# RF_A.net
KiCad netlist of a schematic drawn in Altium Designer
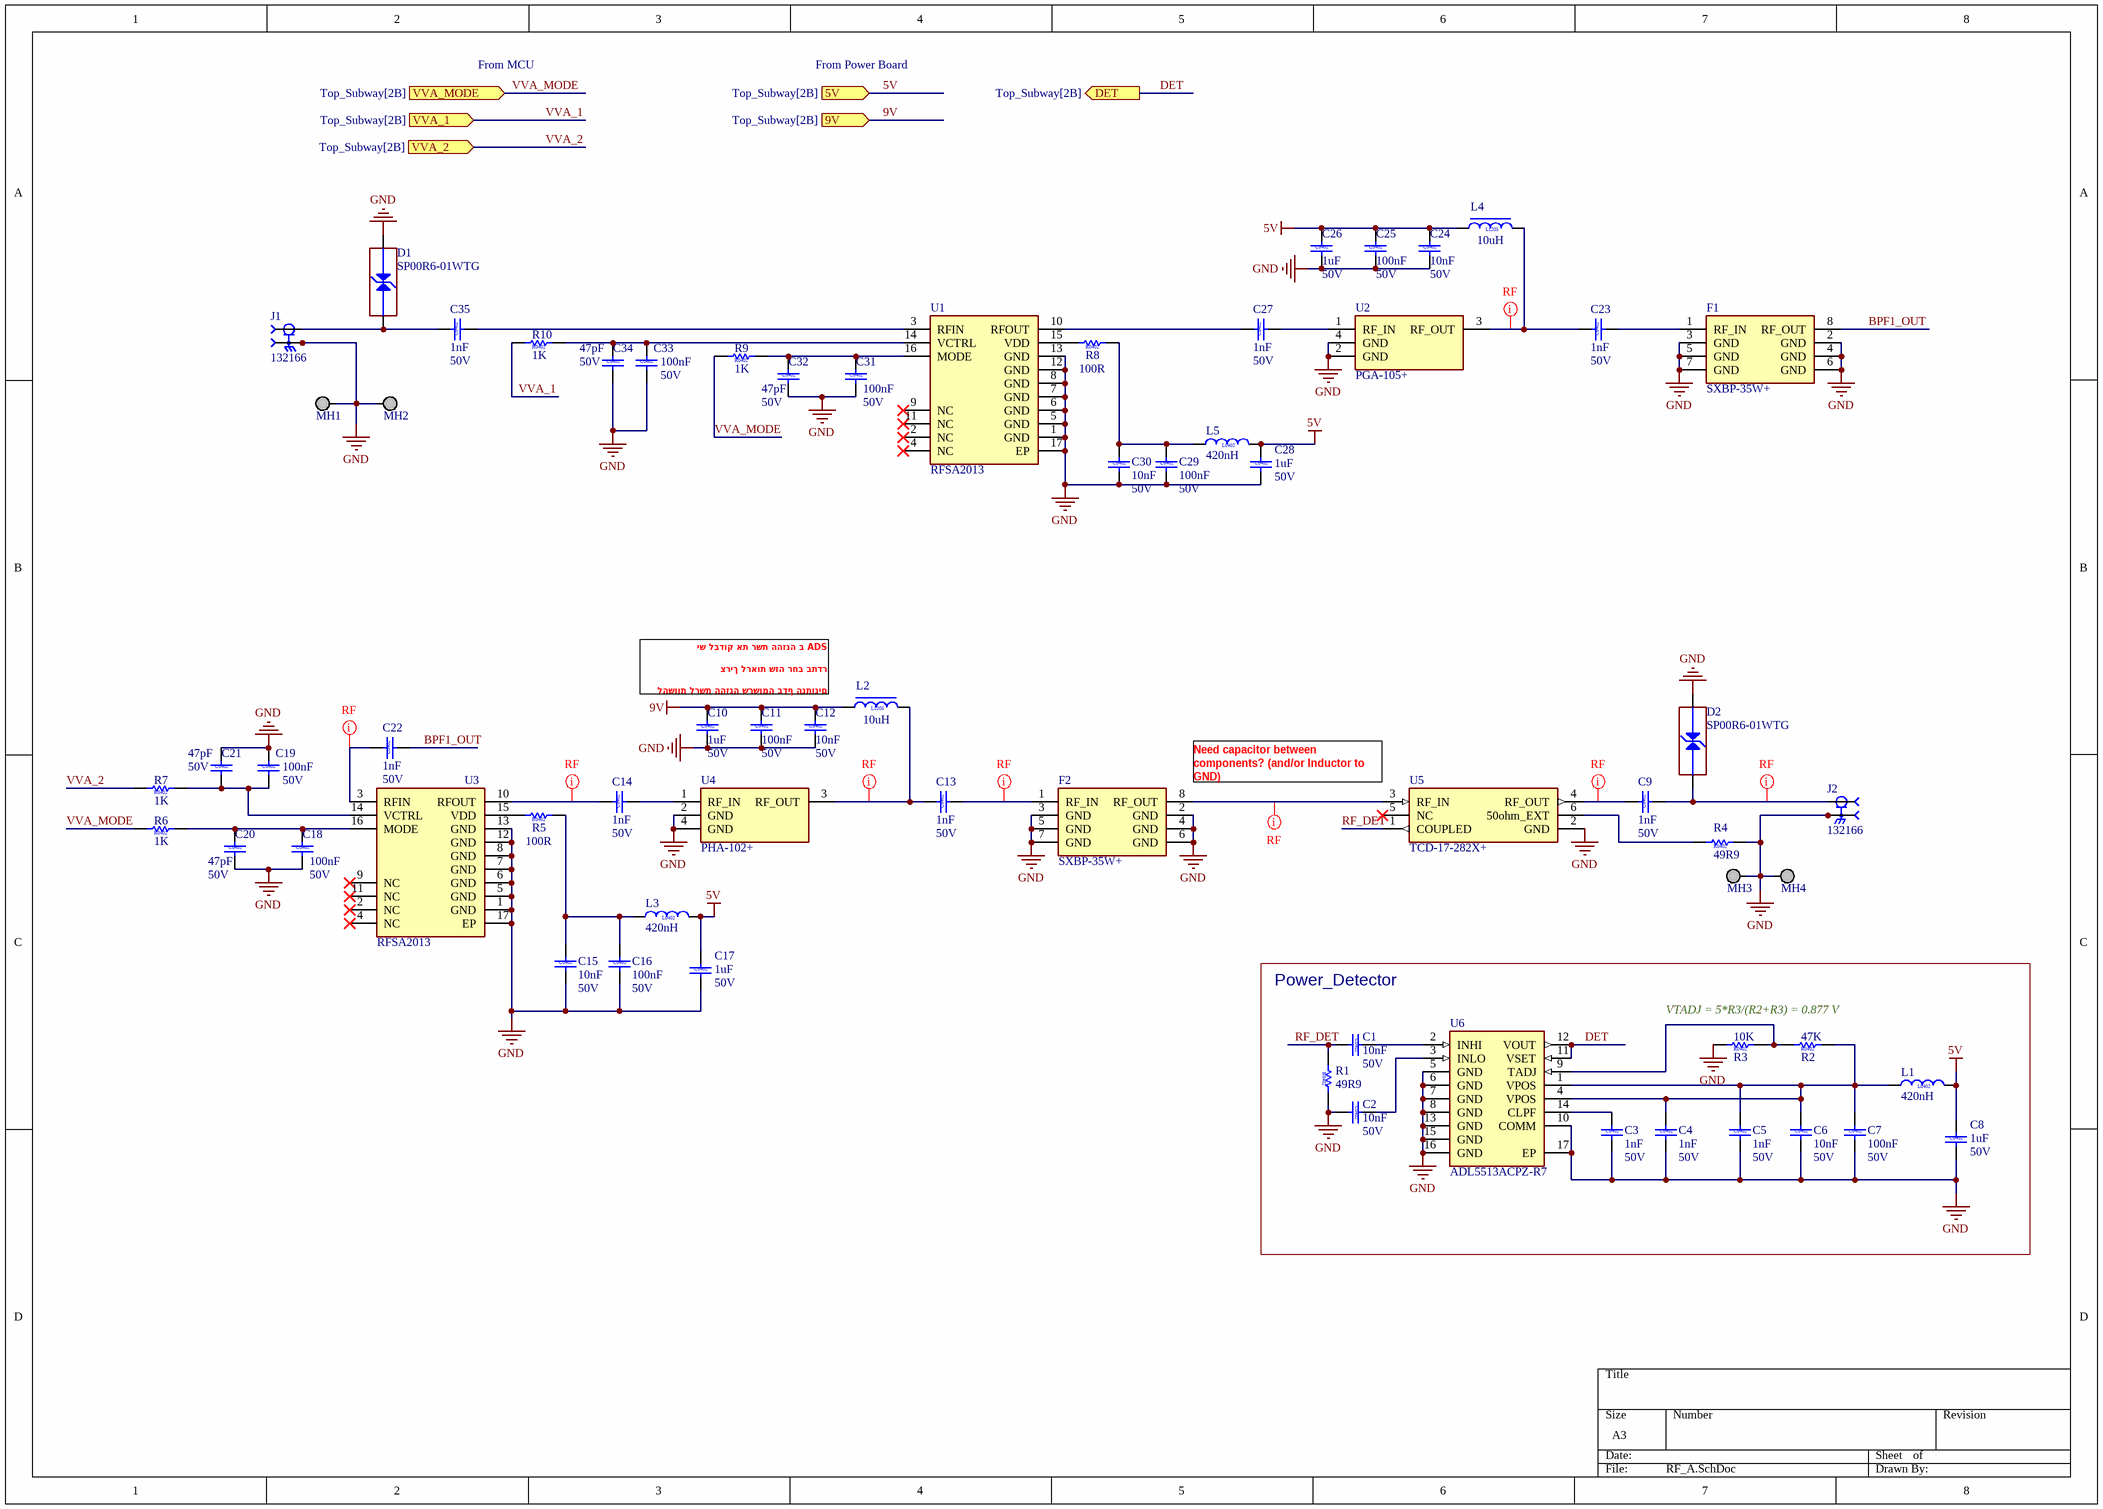
[diagram p0: RF_A.SchDoc]

(export (version "E")
  (design (tool "Eeschema 10.0.6"))
  (components
    (comp (ref "C1")
      (value "10nF")
      (footprint "C0402")
      (description "Capacitor, MLCC, 10nF, 50V, X7R, 10%, 0402, T=0.5mm")
      (fields
        (field (name "MANUFACTURER_PART_NUMBER") "GRM155R71H103KA88D")
        (field (name "MANUFACTURER") "MURATA")
        (field (name "VOLTAGE_RATING") "50V")
      )
      (libsource (lib "CAP_Lib") (part "CAP-103"))
    )
    (comp (ref "C2")
      (value "10nF")
      (footprint "C0402")
      (description "Capacitor, MLCC, 10nF, 50V, X7R, 10%, 0402, T=0.5mm")
      (fields
        (field (name "MANUFACTURER_PART_NUMBER") "GRM155R71H103KA88D")
        (field (name "MANUFACTURER") "MURATA")
        (field (name "VOLTAGE_RATING") "50V")
      )
      (libsource (lib "CAP_Lib") (part "CAP-103"))
    )
    (comp (ref "C3")
      (value "1nF")
      (footprint "C0402")
      (description "Capacitor, MLCC, 1nF, 50V, X7R, 10%, 0402, T=0.5mm")
      (fields
        (field (name "MANUFACTURER_PART_NUMBER") "GRM155R71H102KA01D")
        (field (name "MANUFACTURER") "MURATA")
        (field (name "VOLTAGE_RATING") "50V")
      )
      (libsource (lib "CAP_Lib") (part "CAP-102"))
    )
    (comp (ref "C4")
      (value "1nF")
      (footprint "C0402")
      (description "Capacitor, MLCC, 1nF, 50V, X7R, 10%, 0402, T=0.5mm")
      (fields
        (field (name "MANUFACTURER_PART_NUMBER") "GRM155R71H102KA01D")
        (field (name "MANUFACTURER") "MURATA")
        (field (name "VOLTAGE_RATING") "50V")
      )
      (libsource (lib "CAP_Lib") (part "CAP-102"))
    )
    (comp (ref "C5")
      (value "1nF")
      (footprint "C0402")
      (description "Capacitor, MLCC, 1nF, 50V, X7R, 10%, 0402, T=0.5mm")
      (fields
        (field (name "MANUFACTURER_PART_NUMBER") "GRM155R71H102KA01D")
        (field (name "MANUFACTURER") "MURATA")
        (field (name "VOLTAGE_RATING") "50V")
      )
      (libsource (lib "CAP_Lib") (part "CAP-102"))
    )
    (comp (ref "C6")
      (value "10nF")
      (footprint "C0402")
      (description "Capacitor, MLCC, 10nF, 50V, X7R, 10%, 0402, T=0.5mm")
      (fields
        (field (name "MANUFACTURER_PART_NUMBER") "GRM155R71H103KA88D")
        (field (name "MANUFACTURER") "MURATA")
        (field (name "VOLTAGE_RATING") "50V")
      )
      (libsource (lib "CAP_Lib") (part "CAP-103"))
    )
    (comp (ref "C7")
      (value "100nF")
      (footprint "C0402")
      (description "Capacitor, MLCC, 100nF, 50V, X7R, 10%, 0402, T=0.5mm")
      (fields
        (field (name "MANUFACTURER_PART_NUMBER") "GRM155R71H104KE14D")
        (field (name "MANUFACTURER") "MURATA")
        (field (name "VOLTAGE_RATING") "50V")
      )
      (libsource (lib "CAP_Lib") (part "CAP-104"))
    )
    (comp (ref "C8")
      (value "1uF")
      (footprint "C0402")
      (description "Capacitor, MLCC, 1uF, 50V, X5R, 10%, 0402, T=0.5mm")
      (fields
        (field (name "MANUFACTURER_PART_NUMBER") "GRM155R61H105KE05D")
        (field (name "MANUFACTURER") "MURATA")
        (field (name "VOLTAGE_RATING") "50V")
      )
      (libsource (lib "CAP_Lib") (part "CAP-001"))
    )
    (comp (ref "C9")
      (value "1nF")
      (footprint "C0402")
      (description "Capacitor, MLCC, 1nF, 50V, X7R, 10%, 0402, T=0.5mm")
      (fields
        (field (name "MANUFACTURER_PART_NUMBER") "GRM155R71H102KA01D")
        (field (name "MANUFACTURER") "MURATA")
        (field (name "VOLTAGE_RATING") "50V")
      )
      (libsource (lib "CAP_Lib") (part "CAP-102"))
    )
    (comp (ref "C10")
      (value "1uF")
      (footprint "C0402")
      (description "Capacitor, MLCC, 1uF, 50V, X5R, 10%, 0402, T=0.5mm")
      (fields
        (field (name "MANUFACTURER_PART_NUMBER") "GRM155R61H105KE05D")
        (field (name "MANUFACTURER") "MURATA")
        (field (name "VOLTAGE_RATING") "50V")
      )
      (libsource (lib "CAP_Lib") (part "CAP-001"))
    )
    (comp (ref "C11")
      (value "100nF")
      (footprint "C0402")
      (description "Capacitor, MLCC, 100nF, 50V, X7R, 10%, 0402, T=0.5mm")
      (fields
        (field (name "MANUFACTURER_PART_NUMBER") "GRM155R71H104KE14D")
        (field (name "MANUFACTURER") "MURATA")
        (field (name "VOLTAGE_RATING") "50V")
      )
      (libsource (lib "CAP_Lib") (part "CAP-104"))
    )
    (comp (ref "C12")
      (value "10nF")
      (footprint "C0402")
      (description "Capacitor, MLCC, 10nF, 50V, X7R, 10%, 0402, T=0.5mm")
      (fields
        (field (name "MANUFACTURER_PART_NUMBER") "GRM155R71H103KA88D")
        (field (name "MANUFACTURER") "MURATA")
        (field (name "VOLTAGE_RATING") "50V")
      )
      (libsource (lib "CAP_Lib") (part "CAP-103"))
    )
    (comp (ref "C13")
      (value "1nF")
      (footprint "C0402")
      (description "Capacitor, MLCC, 1nF, 50V, X7R, 10%, 0402, T=0.5mm")
      (fields
        (field (name "MANUFACTURER_PART_NUMBER") "GRM155R71H102KA01D")
        (field (name "MANUFACTURER") "MURATA")
        (field (name "VOLTAGE_RATING") "50V")
      )
      (libsource (lib "CAP_Lib") (part "CAP-102"))
    )
    (comp (ref "C14")
      (value "1nF")
      (footprint "C0402")
      (description "Capacitor, MLCC, 1nF, 50V, X7R, 10%, 0402, T=0.5mm")
      (fields
        (field (name "MANUFACTURER_PART_NUMBER") "GRM155R71H102KA01D")
        (field (name "MANUFACTURER") "MURATA")
        (field (name "VOLTAGE_RATING") "50V")
      )
      (libsource (lib "CAP_Lib") (part "CAP-102"))
    )
    (comp (ref "C15")
      (value "10nF")
      (footprint "C0402")
      (description "Capacitor, MLCC, 10nF, 50V, X7R, 10%, 0402, T=0.5mm")
      (fields
        (field (name "MANUFACTURER_PART_NUMBER") "GRM155R71H103KA88D")
        (field (name "MANUFACTURER") "MURATA")
        (field (name "VOLTAGE_RATING") "50V")
      )
      (libsource (lib "CAP_Lib") (part "CAP-103"))
    )
    (comp (ref "C16")
      (value "100nF")
      (footprint "C0402")
      (description "Capacitor, MLCC, 100nF, 50V, X7R, 10%, 0402, T=0.5mm")
      (fields
        (field (name "MANUFACTURER_PART_NUMBER") "GRM155R71H104KE14D")
        (field (name "MANUFACTURER") "MURATA")
        (field (name "VOLTAGE_RATING") "50V")
      )
      (libsource (lib "CAP_Lib") (part "CAP-104"))
    )
    (comp (ref "C17")
      (value "1uF")
      (footprint "C0402")
      (description "Capacitor, MLCC, 1uF, 50V, X5R, 10%, 0402, T=0.5mm")
      (fields
        (field (name "MANUFACTURER_PART_NUMBER") "GRM155R61H105KE05D")
        (field (name "MANUFACTURER") "MURATA")
        (field (name "VOLTAGE_RATING") "50V")
      )
      (libsource (lib "CAP_Lib") (part "CAP-001"))
    )
    (comp (ref "C18")
      (value "100nF")
      (footprint "C0402")
      (description "Capacitor, MLCC, 100nF, 50V, X7R, 10%, 0402, T=0.5mm")
      (fields
        (field (name "MANUFACTURER_PART_NUMBER") "GRM155R71H104KE14D")
        (field (name "MANUFACTURER") "MURATA")
        (field (name "VOLTAGE_RATING") "50V")
      )
      (libsource (lib "CAP_Lib") (part "CAP-104"))
    )
    (comp (ref "C19")
      (value "100nF")
      (footprint "C0402")
      (description "Capacitor, MLCC, 100nF, 50V, X7R, 10%, 0402, T=0.5mm")
      (fields
        (field (name "MANUFACTURER_PART_NUMBER") "GRM155R71H104KE14D")
        (field (name "MANUFACTURER") "MURATA")
        (field (name "VOLTAGE_RATING") "50V")
      )
      (libsource (lib "CAP_Lib") (part "CAP-104"))
    )
    (comp (ref "C20")
      (value "47pF")
      (footprint "C0402")
      (description "Capacitor, MLCC, 47pF, 50V, C0G 2%, 0402, T=0.5mm")
      (fields
        (field (name "MANUFACTURER_PART_NUMBER") "GRM1555C1H470FA01D")
        (field (name "MANUFACTURER") "MURATA")
        (field (name "VOLTAGE_RATING") "50V")
      )
      (libsource (lib "CAP_Lib") (part "CAP-207"))
    )
    (comp (ref "C21")
      (value "47pF")
      (footprint "C0402")
      (description "Capacitor, MLCC, 47pF, 50V, C0G 2%, 0402, T=0.5mm")
      (fields
        (field (name "MANUFACTURER_PART_NUMBER") "GRM1555C1H470FA01D")
        (field (name "MANUFACTURER") "MURATA")
        (field (name "VOLTAGE_RATING") "50V")
      )
      (libsource (lib "CAP_Lib") (part "CAP-207"))
    )
    (comp (ref "C22")
      (value "1nF")
      (footprint "C0402")
      (description "Capacitor, MLCC, 1nF, 50V, X7R, 10%, 0402, T=0.5mm")
      (fields
        (field (name "MANUFACTURER_PART_NUMBER") "GRM155R71H102KA01D")
        (field (name "MANUFACTURER") "MURATA")
        (field (name "VOLTAGE_RATING") "50V")
      )
      (libsource (lib "CAP_Lib") (part "CAP-102"))
    )
    (comp (ref "C23")
      (value "1nF")
      (footprint "C0402")
      (description "Capacitor, MLCC, 1nF, 50V, X7R, 10%, 0402, T=0.5mm")
      (fields
        (field (name "MANUFACTURER_PART_NUMBER") "GRM155R71H102KA01D")
        (field (name "MANUFACTURER") "MURATA")
        (field (name "VOLTAGE_RATING") "50V")
      )
      (libsource (lib "CAP_Lib") (part "CAP-102"))
    )
    (comp (ref "C24")
      (value "10nF")
      (footprint "C0402")
      (description "Capacitor, MLCC, 10nF, 50V, X7R, 10%, 0402, T=0.5mm")
      (fields
        (field (name "MANUFACTURER_PART_NUMBER") "GRM155R71H103KA88D")
        (field (name "MANUFACTURER") "MURATA")
        (field (name "VOLTAGE_RATING") "50V")
      )
      (libsource (lib "CAP_Lib") (part "CAP-103"))
    )
    (comp (ref "C25")
      (value "100nF")
      (footprint "C0402")
      (description "Capacitor, MLCC, 100nF, 50V, X7R, 10%, 0402, T=0.5mm")
      (fields
        (field (name "MANUFACTURER_PART_NUMBER") "GRM155R71H104KE14D")
        (field (name "MANUFACTURER") "MURATA")
        (field (name "VOLTAGE_RATING") "50V")
      )
      (libsource (lib "CAP_Lib") (part "CAP-104"))
    )
    (comp (ref "C26")
      (value "1uF")
      (footprint "C0402")
      (description "Capacitor, MLCC, 1uF, 50V, X5R, 10%, 0402, T=0.5mm")
      (fields
        (field (name "MANUFACTURER_PART_NUMBER") "GRM155R61H105KE05D")
        (field (name "MANUFACTURER") "MURATA")
        (field (name "VOLTAGE_RATING") "50V")
      )
      (libsource (lib "CAP_Lib") (part "CAP-001"))
    )
    (comp (ref "C27")
      (value "1nF")
      (footprint "C0402")
      (description "Capacitor, MLCC, 1nF, 50V, X7R, 10%, 0402, T=0.5mm")
      (fields
        (field (name "MANUFACTURER_PART_NUMBER") "GRM155R71H102KA01D")
        (field (name "MANUFACTURER") "MURATA")
        (field (name "VOLTAGE_RATING") "50V")
      )
      (libsource (lib "CAP_Lib") (part "CAP-102"))
    )
    (comp (ref "C28")
      (value "1uF")
      (footprint "C0402")
      (description "Capacitor, MLCC, 1uF, 50V, X5R, 10%, 0402, T=0.5mm")
      (fields
        (field (name "MANUFACTURER_PART_NUMBER") "GRM155R61H105KE05D")
        (field (name "MANUFACTURER") "MURATA")
        (field (name "VOLTAGE_RATING") "50V")
      )
      (libsource (lib "CAP_Lib") (part "CAP-001"))
    )
    (comp (ref "C29")
      (value "100nF")
      (footprint "C0402")
      (description "Capacitor, MLCC, 100nF, 50V, X7R, 10%, 0402, T=0.5mm")
      (fields
        (field (name "MANUFACTURER_PART_NUMBER") "GRM155R71H104KE14D")
        (field (name "MANUFACTURER") "MURATA")
        (field (name "VOLTAGE_RATING") "50V")
      )
      (libsource (lib "CAP_Lib") (part "CAP-104"))
    )
    (comp (ref "C30")
      (value "10nF")
      (footprint "C0402")
      (description "Capacitor, MLCC, 10nF, 50V, X7R, 10%, 0402, T=0.5mm")
      (fields
        (field (name "MANUFACTURER_PART_NUMBER") "GRM155R71H103KA88D")
        (field (name "MANUFACTURER") "MURATA")
        (field (name "VOLTAGE_RATING") "50V")
      )
      (libsource (lib "CAP_Lib") (part "CAP-103"))
    )
    (comp (ref "C31")
      (value "100nF")
      (footprint "C0402")
      (description "Capacitor, MLCC, 100nF, 50V, X7R, 10%, 0402, T=0.5mm")
      (fields
        (field (name "MANUFACTURER_PART_NUMBER") "GRM155R71H104KE14D")
        (field (name "MANUFACTURER") "MURATA")
        (field (name "VOLTAGE_RATING") "50V")
      )
      (libsource (lib "CAP_Lib") (part "CAP-104"))
    )
    (comp (ref "C32")
      (value "47pF")
      (footprint "C0402")
      (description "Capacitor, MLCC, 47pF, 50V, C0G 2%, 0402, T=0.5mm")
      (fields
        (field (name "MANUFACTURER_PART_NUMBER") "GRM1555C1H470FA01D")
        (field (name "MANUFACTURER") "MURATA")
        (field (name "VOLTAGE_RATING") "50V")
      )
      (libsource (lib "CAP_Lib") (part "CAP-207"))
    )
    (comp (ref "C33")
      (value "100nF")
      (footprint "C0402")
      (description "Capacitor, MLCC, 100nF, 50V, X7R, 10%, 0402, T=0.5mm")
      (fields
        (field (name "MANUFACTURER_PART_NUMBER") "GRM155R71H104KE14D")
        (field (name "MANUFACTURER") "MURATA")
        (field (name "VOLTAGE_RATING") "50V")
      )
      (libsource (lib "CAP_Lib") (part "CAP-104"))
    )
    (comp (ref "C34")
      (value "47pF")
      (footprint "C0402")
      (description "Capacitor, MLCC, 47pF, 50V, C0G 2%, 0402, T=0.5mm")
      (fields
        (field (name "MANUFACTURER_PART_NUMBER") "GRM1555C1H470FA01D")
        (field (name "MANUFACTURER") "MURATA")
        (field (name "VOLTAGE_RATING") "50V")
      )
      (libsource (lib "CAP_Lib") (part "CAP-207"))
    )
    (comp (ref "C35")
      (value "1nF")
      (footprint "C0402")
      (description "Capacitor, MLCC, 1nF, 50V, X7R, 10%, 0402, T=0.5mm")
      (fields
        (field (name "MANUFACTURER_PART_NUMBER") "GRM155R71H102KA01D")
        (field (name "MANUFACTURER") "MURATA")
        (field (name "VOLTAGE_RATING") "50V")
      )
      (libsource (lib "CAP_Lib") (part "CAP-102"))
    )
    (comp (ref "D1")
      (value "SP00R6-01WTG")
      (footprint "DIO_TVS_FLIPCHIP2")
      (description "Diode, TVS, Bidirectional, 0.3V working, 0.7V breakdown, 2.5V clamping, 3A")
      (fields
        (field (name "MANUFACTURER") "Littelfuse")
        (field (name "MOUSER PART NUMBER") "576-SP00R6-01WTG")
      )
      (libsource (lib "DIO_Lib") (part "DIO-012"))
    )
    (comp (ref "D2")
      (value "SP00R6-01WTG")
      (footprint "DIO_TVS_FLIPCHIP2")
      (description "Diode, TVS, Bidirectional, 0.3V working, 0.7V breakdown, 2.5V clamping, 3A")
      (fields
        (field (name "MANUFACTURER") "Littelfuse")
        (field (name "MOUSER PART NUMBER") "576-SP00R6-01WTG")
      )
      (libsource (lib "DIO_Lib") (part "DIO-012"))
    )
    (comp (ref "F1")
      (value "SXBP-35W+")
      (footprint "FIL_HF1139")
      (description "Filter, BPF, 24-46MHz, 1dB IL")
      (fields (field (name "MANUFACTURER") "Mini-Circuits"))
      (libsource (lib "RFC_Lib") (part "RFC-234"))
    )
    (comp (ref "F2")
      (value "SXBP-35W+")
      (footprint "FIL_HF1139")
      (description "Filter, BPF, 24-46MHz, 1dB IL")
      (fields (field (name "MANUFACTURER") "Mini-Circuits"))
      (libsource (lib "RFC_Lib") (part "RFC-218"))
    )
    (comp (ref "J1")
      (value "132166")
      (footprint "CON_SMA_132166")
      (description "Connector, SMA Jack, Female Socket 50Ohm, DC-12.4GHz, Flange Mount")
      (fields (field (name "MANUFACTURER") "Amphenol"))
      (libsource (lib "CON_Lib") (part "CON-304"))
    )
    (comp (ref "J2")
      (value "132166")
      (footprint "CON_SMA_132166")
      (description "Connector, SMA Jack, Female Socket 50Ohm, DC-12.4GHz, Flange Mount")
      (fields (field (name "MANUFACTURER") "Amphenol"))
      (libsource (lib "CON_Lib") (part "CON-304"))
    )
    (comp (ref "L1")
      (value "420nH")
      (footprint "L0402DF")
      (description "Inductor, RF, 420nH, 400mA, 510mOhm DCR, 1100MHz SRF, 5%, 0402, 0.66mm")
      (fields
        (field (name "MANUFACTURER") "COILCRAFT")
        (field (name "MANUFACTURER_PART_NUMBER") "0402DF-421XJRW")
      )
      (libsource (lib "IND_Lib") (part "IND-102"))
    )
    (comp (ref "L2")
      (value "10uH")
      (footprint "L1205POC")
      (description "RF Choke,10uH, 560mA, 1Ohm DCR, 165MHz SRF, 20%, 1205, 2.36mm")
      (fields
        (field (name "MANUFACTURER") "COILCRAFT")
        (field (name "MANUFACTURER_PART_NUMBER") "1205POC-103MRC")
      )
      (libsource (lib "IND_Lib") (part "IND-301"))
    )
    (comp (ref "L3")
      (value "420nH")
      (footprint "L0402DF")
      (description "Inductor, RF, 420nH, 400mA, 510mOhm DCR, 1100MHz SRF, 5%, 0402, 0.66mm")
      (fields
        (field (name "MANUFACTURER") "COILCRAFT")
        (field (name "MANUFACTURER_PART_NUMBER") "0402DF-421XJRW")
      )
      (libsource (lib "IND_Lib") (part "IND-102"))
    )
    (comp (ref "L4")
      (value "10uH")
      (footprint "L1205POC")
      (description "RF Choke,10uH, 560mA, 1Ohm DCR, 165MHz SRF, 20%, 1205, 2.36mm")
      (fields
        (field (name "MANUFACTURER") "COILCRAFT")
        (field (name "MANUFACTURER_PART_NUMBER") "1205POC-103MRC")
      )
      (libsource (lib "IND_Lib") (part "IND-301"))
    )
    (comp (ref "L5")
      (value "420nH")
      (footprint "L0402DF")
      (description "Inductor, RF, 420nH, 400mA, 510mOhm DCR, 1100MHz SRF, 5%, 0402, 0.66mm")
      (fields
        (field (name "MANUFACTURER") "COILCRAFT")
        (field (name "MANUFACTURER_PART_NUMBER") "0402DF-421XJRW")
      )
      (libsource (lib "IND_Lib") (part "IND-102"))
    )
    (comp (ref "MH1")
      (value "Mounting Hole 2.4mm")
      (footprint "MH_TH_2P4MM")
      (description "Mounting Hole 2.4mm drill hole")
      (libsource (lib "MEC_Lib") (part "MEC-005"))
    )
    (comp (ref "MH2")
      (value "Mounting Hole 2.4mm")
      (footprint "MH_TH_2P4MM")
      (description "Mounting Hole 2.4mm drill hole")
      (libsource (lib "MEC_Lib") (part "MEC-005"))
    )
    (comp (ref "MH3")
      (value "Mounting Hole 2.4mm")
      (footprint "MH_TH_2P4MM")
      (description "Mounting Hole 2.4mm drill hole")
      (libsource (lib "MEC_Lib") (part "MEC-005"))
    )
    (comp (ref "MH4")
      (value "Mounting Hole 2.4mm")
      (footprint "MH_TH_2P4MM")
      (description "Mounting Hole 2.4mm drill hole")
      (libsource (lib "MEC_Lib") (part "MEC-005"))
    )
    (comp (ref "R1")
      (value "49R9")
      (footprint "R0402")
      (description "Resistor,49R9,0402,1%,1/16W")
      (fields
        (field (name "MANUFACTURER_PART_NUMBER") "RC0402FR-0749R9L")
        (field (name "MANUFACTURER") "YAGEO")
      )
      (libsource (lib "RES_Lib") (part "RES-104"))
    )
    (comp (ref "R2")
      (value "47K")
      (footprint "R0402")
      (description "Resistor,47K,0402,1%,1/16W")
      (fields
        (field (name "MANUFACTURER_PART_NUMBER") "RC0402FR-0747KL")
        (field (name "MANUFACTURER") "YAGEO")
      )
      (libsource (lib "RES_Lib") (part "RES-011"))
    )
    (comp (ref "R3")
      (value "10K")
      (footprint "R0402")
      (description "Resistor,10K,0402,1%,1/16W")
      (fields
        (field (name "MANUFACTURER_PART_NUMBER") "RC0402FR-0710KL")
        (field (name "MANUFACTURER") "YAGEO")
      )
      (libsource (lib "RES_Lib") (part "RES-007"))
    )
    (comp (ref "R4")
      (value "49R9")
      (footprint "R0402")
      (description "Resistor,49R9,0402,1%,1/16W")
      (fields
        (field (name "MANUFACTURER_PART_NUMBER") "RC0402FR-0749R9L")
        (field (name "MANUFACTURER") "YAGEO")
      )
      (libsource (lib "RES_Lib") (part "RES-104"))
    )
    (comp (ref "R5")
      (value "100R")
      (footprint "R0402")
      (description "Resistor,100R,0402,1%,1/16W")
      (fields
        (field (name "MANUFACTURER_PART_NUMBER") "RC0402FR-07100RL")
        (field (name "MANUFACTURER") "YAGEO")
        (field (name "PROVIDED_BY") "SUBCO")
      )
      (libsource (lib "RES_Lib") (part "RES-106"))
    )
    (comp (ref "R6")
      (value "1K")
      (footprint "R0402")
      (description "Resistor,1K,0402,1%,1/16W")
      (fields
        (field (name "MANUFACTURER_PART_NUMBER") "RC0402FR-071KL")
        (field (name "MANUFACTURER") "YAGEO")
      )
      (libsource (lib "RES_Lib") (part "RES-001"))
    )
    (comp (ref "R7")
      (value "1K")
      (footprint "R0402")
      (description "Resistor,1K,0402,1%,1/16W")
      (fields
        (field (name "MANUFACTURER_PART_NUMBER") "RC0402FR-071KL")
        (field (name "MANUFACTURER") "YAGEO")
      )
      (libsource (lib "RES_Lib") (part "RES-001"))
    )
    (comp (ref "R8")
      (value "100R")
      (footprint "R0402")
      (description "Resistor,100R,0402,1%,1/16W")
      (fields
        (field (name "MANUFACTURER_PART_NUMBER") "RC0402FR-07100RL")
        (field (name "MANUFACTURER") "YAGEO")
        (field (name "PROVIDED_BY") "SUBCO")
      )
      (libsource (lib "RES_Lib") (part "RES-106"))
    )
    (comp (ref "R9")
      (value "1K")
      (footprint "R0402")
      (description "Resistor,1K,0402,1%,1/16W")
      (fields
        (field (name "MANUFACTURER_PART_NUMBER") "RC0402FR-071KL")
        (field (name "MANUFACTURER") "YAGEO")
      )
      (libsource (lib "RES_Lib") (part "RES-001"))
    )
    (comp (ref "R10")
      (value "1K")
      (footprint "R0402")
      (description "Resistor,1K,0402,1%,1/16W")
      (fields
        (field (name "MANUFACTURER_PART_NUMBER") "RC0402FR-071KL")
        (field (name "MANUFACTURER") "YAGEO")
      )
      (libsource (lib "RES_Lib") (part "RES-001"))
    )
    (comp (ref "U1")
      (value "RFSA2013")
      (footprint "VVA_QFN-16")
      (description "VVA, RF Attenuator 2.6-35dB .05-6GHz\r\n0-5VC")
      (fields (field (name "MANUFACTURER") "Qorvo") (field (name "MANUFACTURER_PART_NUMBER") "RFSA2013TR7"))
      (libsource (lib "RFC_Lib") (part "RFC-107"))
    )
    (comp (ref "U2")
      (value "PGA-105+")
      (footprint "AMP_DF782")
      (description "LNA, RF Amplifier .04-2.6GHz Gain 15-16.5dB, NF 1.7-2.1dB, OIP3 33-39dBm, 5V")
      (fields (field (name "MANUFACTURER") "Mini-Circuits") (field (name "MOUSER PART NUMBER") "139-PGA-105"))
      (libsource (lib "RFC_Lib") (part "RFC-109"))
    )
    (comp (ref "U3")
      (value "RFSA2013")
      (footprint "VVA_QFN-16")
      (description "VVA, RF Attenuator 2.6-35dB .05-6GHz\r\n0-5VC")
      (fields (field (name "MANUFACTURER") "Qorvo") (field (name "MANUFACTURER_PART_NUMBER") "RFSA2013TR7"))
      (libsource (lib "RFC_Lib") (part "RFC-107"))
    )
    (comp (ref "U4")
      (value "PHA-102+")
      (footprint "AMP_DF782")
      (description "RF Amplifier, High Linearity, .05-6GHz Gain 14.6dB, NF 3.5dB, OIP3 45-50dBm, 9V")
      (fields
        (field (name "MANUFACTURER") "Mini-Circuits")
        (field (name "MOUSER PART NUMBER") "139-PHA-102+")
      )
      (libsource (lib "RFC_Lib") (part "RFC-106"))
    )
    (comp (ref "U5")
      (value "TCD-17-282X+")
      (footprint "SPLT_COUP_DB1627")
      (description "Coupler, 5-2850MHz, 0.7-1.9dB IL, 17dB Coupling")
      (fields
        (field (name "MANUFACTURER") "Mini-Circuits")
        (field (name "MOUSER PART NUMBER") "139-TCD-17-282X")
      )
      (libsource (lib "RFC_Lib") (part "RFC-301"))
    )
    (comp (ref "U6")
      (value "ADL5513ACPZ-R7")
      (footprint "PWD_QFN50P300X300X80-17N-D")
      (description "Power Detector, RF Detector Next Gen 75 dB Log Detector")
      (fields
        (field (name "MANUFACTURER") "Analog Devices")
        (field (name "MOUSER PART NUMBER") "584-ADL5513ACPZ-R7")
      )
      (libsource (lib "RFC_Lib") (part "RFC-104"))
    )
  )
  (nets
    (net (code "1") (name "/BPF1_OUT") (class "Default")
      (node (ref "C22") (pin "1") (pinfunction "1_1") (pintype "passive"))
      (node (ref "F1") (pin "8") (pinfunction "RF_OUT_8") (pintype "passive"))
    )
    (net (code "2") (name "/DET") (class "Default")
      (node (ref "U6") (pin "11") (pinfunction "VSET_11") (pintype "input"))
      (node (ref "U6") (pin "12") (pinfunction "VOUT_12") (pintype "output"))
    )
    (net (code "3") (name "/RF_DET") (class "Default")
      (node (ref "C1") (pin "1") (pinfunction "1_1") (pintype "passive"))
      (node (ref "R1") (pin "1") (pinfunction "1_1") (pintype "passive"))
      (node (ref "U5") (pin "1") (pinfunction "COUPLED_1") (pintype "output"))
    )
    (net (code "4") (name "/VVA_1") (class "Default")
      (node (ref "R10") (pin "1") (pinfunction "1_1") (pintype "passive"))
    )
    (net (code "5") (name "/VVA_2") (class "Default")
      (node (ref "R7") (pin "1") (pinfunction "1_1") (pintype "passive"))
    )
    (net (code "6") (name "/VVA_MODE") (class "Default")
      (node (ref "R6") (pin "1") (pinfunction "1_1") (pintype "passive"))
      (node (ref "R9") (pin "1") (pinfunction "1_1") (pintype "passive"))
    )
    (net (code "7") (name "5V") (class "Default")
      (node (ref "C17") (pin "2") (pinfunction "2_2") (pintype "passive"))
      (node (ref "C24") (pin "2") (pinfunction "2_2") (pintype "passive"))
      (node (ref "C25") (pin "2") (pinfunction "2_2") (pintype "passive"))
      (node (ref "C26") (pin "2") (pinfunction "2_2") (pintype "passive"))
      (node (ref "C28") (pin "2") (pinfunction "2_2") (pintype "passive"))
      (node (ref "C8") (pin "2") (pinfunction "2_2") (pintype "passive"))
      (node (ref "L1") (pin "2") (pinfunction "2_2") (pintype "passive"))
      (node (ref "L3") (pin "2") (pinfunction "2_2") (pintype "passive"))
      (node (ref "L4") (pin "1") (pinfunction "1_1") (pintype "passive"))
      (node (ref "L5") (pin "2") (pinfunction "2_2") (pintype "passive"))
    )
    (net (code "8") (name "9V") (class "Default")
      (node (ref "C10") (pin "2") (pinfunction "2_2") (pintype "passive"))
      (node (ref "C11") (pin "2") (pinfunction "2_2") (pintype "passive"))
      (node (ref "C12") (pin "2") (pinfunction "2_2") (pintype "passive"))
      (node (ref "L2") (pin "1") (pinfunction "1_1") (pintype "passive"))
    )
    (net (code "9") (name "GND") (class "Default")
      (node (ref "C10") (pin "1") (pinfunction "1_1") (pintype "passive"))
      (node (ref "C11") (pin "1") (pinfunction "1_1") (pintype "passive"))
      (node (ref "C12") (pin "1") (pinfunction "1_1") (pintype "passive"))
      (node (ref "C15") (pin "1") (pinfunction "1_1") (pintype "passive"))
      (node (ref "C16") (pin "1") (pinfunction "1_1") (pintype "passive"))
      (node (ref "C17") (pin "1") (pinfunction "1_1") (pintype "passive"))
      (node (ref "C18") (pin "1") (pinfunction "1_1") (pintype "passive"))
      (node (ref "C19") (pin "2") (pinfunction "2_2") (pintype "passive"))
      (node (ref "C2") (pin "1") (pinfunction "1_1") (pintype "passive"))
      (node (ref "C20") (pin "1") (pinfunction "1_1") (pintype "passive"))
      (node (ref "C21") (pin "2") (pinfunction "2_2") (pintype "passive"))
      (node (ref "C24") (pin "1") (pinfunction "1_1") (pintype "passive"))
      (node (ref "C25") (pin "1") (pinfunction "1_1") (pintype "passive"))
      (node (ref "C26") (pin "1") (pinfunction "1_1") (pintype "passive"))
      (node (ref "C28") (pin "1") (pinfunction "1_1") (pintype "passive"))
      (node (ref "C29") (pin "1") (pinfunction "1_1") (pintype "passive"))
      (node (ref "C3") (pin "1") (pinfunction "1_1") (pintype "passive"))
      (node (ref "C30") (pin "1") (pinfunction "1_1") (pintype "passive"))
      (node (ref "C31") (pin "1") (pinfunction "1_1") (pintype "passive"))
      (node (ref "C32") (pin "1") (pinfunction "1_1") (pintype "passive"))
      (node (ref "C33") (pin "1") (pinfunction "1_1") (pintype "passive"))
      (node (ref "C34") (pin "1") (pinfunction "1_1") (pintype "passive"))
      (node (ref "C4") (pin "1") (pinfunction "1_1") (pintype "passive"))
      (node (ref "C5") (pin "1") (pinfunction "1_1") (pintype "passive"))
      (node (ref "C6") (pin "1") (pinfunction "1_1") (pintype "passive"))
      (node (ref "C7") (pin "1") (pinfunction "1_1") (pintype "passive"))
      (node (ref "C8") (pin "1") (pinfunction "1_1") (pintype "passive"))
      (node (ref "D1") (pin "2") (pinfunction "GND_2") (pintype "passive"))
      (node (ref "D2") (pin "2") (pinfunction "GND_2") (pintype "passive"))
      (node (ref "F1") (pin "2") (pinfunction "GND_2") (pintype "passive"))
      (node (ref "F1") (pin "3") (pinfunction "GND_3") (pintype "passive"))
      (node (ref "F1") (pin "4") (pinfunction "GND_4") (pintype "passive"))
      (node (ref "F1") (pin "5") (pinfunction "GND_5") (pintype "passive"))
      (node (ref "F1") (pin "6") (pinfunction "GND_6") (pintype "passive"))
      (node (ref "F1") (pin "7") (pinfunction "GND_7") (pintype "passive"))
      (node (ref "F2") (pin "2") (pinfunction "GND_2") (pintype "passive"))
      (node (ref "F2") (pin "3") (pinfunction "GND_3") (pintype "passive"))
      (node (ref "F2") (pin "4") (pinfunction "GND_4") (pintype "passive"))
      (node (ref "F2") (pin "5") (pinfunction "GND_5") (pintype "passive"))
      (node (ref "F2") (pin "6") (pinfunction "GND_6") (pintype "passive"))
      (node (ref "F2") (pin "7") (pinfunction "GND_7") (pintype "passive"))
      (node (ref "J1") (pin "2_1") (pinfunction "GND_2_1") (pintype "passive"))
      (node (ref "J1") (pin "2_2") (pinfunction "GND_2_2") (pintype "passive"))
      (node (ref "J1") (pin "3_1") (pinfunction "GND_3_1") (pintype "passive"))
      (node (ref "J1") (pin "3_2") (pinfunction "GND_3_2") (pintype "passive"))
      (node (ref "J2") (pin "2_1") (pinfunction "GND_2_1") (pintype "passive"))
      (node (ref "J2") (pin "2_2") (pinfunction "GND_2_2") (pintype "passive"))
      (node (ref "J2") (pin "3_1") (pinfunction "GND_3_1") (pintype "passive"))
      (node (ref "J2") (pin "3_2") (pinfunction "GND_3_2") (pintype "passive"))
      (node (ref "MH1") (pin "MH") (pinfunction "MH_MH") (pintype "passive"))
      (node (ref "MH2") (pin "MH") (pinfunction "MH_MH") (pintype "passive"))
      (node (ref "MH3") (pin "MH") (pinfunction "MH_MH") (pintype "passive"))
      (node (ref "MH4") (pin "MH") (pinfunction "MH_MH") (pintype "passive"))
      (node (ref "R1") (pin "2") (pinfunction "2_2") (pintype "passive"))
      (node (ref "R3") (pin "1") (pinfunction "1_1") (pintype "passive"))
      (node (ref "R4") (pin "2") (pinfunction "2_2") (pintype "passive"))
      (node (ref "U1") (pin "1") (pinfunction "GND_1") (pintype "passive"))
      (node (ref "U1") (pin "12") (pinfunction "GND_12") (pintype "passive"))
      (node (ref "U1") (pin "13") (pinfunction "GND_13") (pintype "passive"))
      (node (ref "U1") (pin "17") (pinfunction "EP_17") (pintype "passive"))
      (node (ref "U1") (pin "5") (pinfunction "GND_5") (pintype "passive"))
      (node (ref "U1") (pin "6") (pinfunction "GND_6") (pintype "passive"))
      (node (ref "U1") (pin "7") (pinfunction "GND_7") (pintype "passive"))
      (node (ref "U1") (pin "8") (pinfunction "GND_8") (pintype "passive"))
      (node (ref "U2") (pin "2") (pinfunction "GND_2") (pintype "passive"))
      (node (ref "U2") (pin "4") (pinfunction "GND_4") (pintype "passive"))
      (node (ref "U3") (pin "1") (pinfunction "GND_1") (pintype "passive"))
      (node (ref "U3") (pin "12") (pinfunction "GND_12") (pintype "passive"))
      (node (ref "U3") (pin "13") (pinfunction "GND_13") (pintype "passive"))
      (node (ref "U3") (pin "17") (pinfunction "EP_17") (pintype "passive"))
      (node (ref "U3") (pin "5") (pinfunction "GND_5") (pintype "passive"))
      (node (ref "U3") (pin "6") (pinfunction "GND_6") (pintype "passive"))
      (node (ref "U3") (pin "7") (pinfunction "GND_7") (pintype "passive"))
      (node (ref "U3") (pin "8") (pinfunction "GND_8") (pintype "passive"))
      (node (ref "U4") (pin "2") (pinfunction "GND_2") (pintype "passive"))
      (node (ref "U4") (pin "4") (pinfunction "GND_4") (pintype "passive"))
      (node (ref "U5") (pin "2") (pinfunction "GND_2") (pintype "passive"))
      (node (ref "U6") (pin "10") (pinfunction "COMM_10") (pintype "passive"))
      (node (ref "U6") (pin "13") (pinfunction "GND_13") (pintype "passive"))
      (node (ref "U6") (pin "15") (pinfunction "GND_15") (pintype "passive"))
      (node (ref "U6") (pin "16") (pinfunction "GND_16") (pintype "passive"))
      (node (ref "U6") (pin "17") (pinfunction "EP_17") (pintype "passive"))
      (node (ref "U6") (pin "5") (pinfunction "GND_5") (pintype "passive"))
      (node (ref "U6") (pin "6") (pinfunction "GND_6") (pintype "passive"))
      (node (ref "U6") (pin "7") (pinfunction "GND_7") (pintype "passive"))
      (node (ref "U6") (pin "8") (pinfunction "GND_8") (pintype "passive"))
    )
    (net (code "10") (name "Net-(C4-Pad2)") (class "Default")
      (node (ref "C4") (pin "2") (pinfunction "2_2") (pintype "passive"))
      (node (ref "C5") (pin "2") (pinfunction "2_2") (pintype "passive"))
      (node (ref "C6") (pin "2") (pinfunction "2_2") (pintype "passive"))
      (node (ref "C7") (pin "2") (pinfunction "2_2") (pintype "passive"))
      (node (ref "L1") (pin "1") (pinfunction "1_1") (pintype "passive"))
      (node (ref "R2") (pin "2") (pinfunction "2_2") (pintype "passive"))
      (node (ref "U6") (pin "1") (pinfunction "VPOS_1") (pintype "passive"))
      (node (ref "U6") (pin "4") (pinfunction "VPOS_4") (pintype "passive"))
    )
    (net (code "11") (name "Net-(C15-Pad2)") (class "Default")
      (node (ref "C15") (pin "2") (pinfunction "2_2") (pintype "passive"))
      (node (ref "C16") (pin "2") (pinfunction "2_2") (pintype "passive"))
      (node (ref "L3") (pin "1") (pinfunction "1_1") (pintype "passive"))
      (node (ref "R5") (pin "2") (pinfunction "2_2") (pintype "passive"))
    )
    (net (code "12") (name "Net-(C29-Pad2)") (class "Default")
      (node (ref "C29") (pin "2") (pinfunction "2_2") (pintype "passive"))
      (node (ref "C30") (pin "2") (pinfunction "2_2") (pintype "passive"))
      (node (ref "L5") (pin "1") (pinfunction "1_1") (pintype "passive"))
      (node (ref "R8") (pin "2") (pinfunction "2_2") (pintype "passive"))
    )
    (net (code "13") (name "Net-(D1-IO1)") (class "Default")
      (node (ref "C35") (pin "2") (pinfunction "2_2") (pintype "passive"))
      (node (ref "D1") (pin "1") (pinfunction "IO1_1") (pintype "passive"))
      (node (ref "J1") (pin "1") (pinfunction "1_1") (pintype "passive"))
    )
    (net (code "14") (name "Net-(D2-IO1)") (class "Default")
      (node (ref "C9") (pin "1") (pinfunction "1_1") (pintype "passive"))
      (node (ref "D2") (pin "1") (pinfunction "IO1_1") (pintype "passive"))
      (node (ref "J2") (pin "1") (pinfunction "1_1") (pintype "passive"))
    )
    (net (code "15") (name "Net-(F1-RF_IN)") (class "Default")
      (node (ref "C23") (pin "1") (pinfunction "1_1") (pintype "passive"))
      (node (ref "F1") (pin "1") (pinfunction "RF_IN_1") (pintype "passive"))
    )
    (net (code "16") (name "Net-(F2-RF_IN)") (class "Default")
      (node (ref "C13") (pin "1") (pinfunction "1_1") (pintype "passive"))
      (node (ref "F2") (pin "1") (pinfunction "RF_IN_1") (pintype "passive"))
    )
    (net (code "17") (name "Net-(F2-RF_OUT)") (class "Default")
      (node (ref "F2") (pin "8") (pinfunction "RF_OUT_8") (pintype "passive"))
      (node (ref "U5") (pin "3") (pinfunction "RF_IN_3") (pintype "input"))
    )
    (net (code "18") (name "Net-(U1-MODE)") (class "Default")
      (node (ref "C31") (pin "2") (pinfunction "2_2") (pintype "passive"))
      (node (ref "C32") (pin "2") (pinfunction "2_2") (pintype "passive"))
      (node (ref "R9") (pin "2") (pinfunction "2_2") (pintype "passive"))
      (node (ref "U1") (pin "16") (pinfunction "MODE_16") (pintype "passive"))
    )
    (net (code "19") (name "Net-(U1-RFIN)") (class "Default")
      (node (ref "C35") (pin "1") (pinfunction "1_1") (pintype "passive"))
      (node (ref "U1") (pin "3") (pinfunction "RFIN_3") (pintype "passive"))
    )
    (net (code "20") (name "Net-(U1-RFOUT)") (class "Default")
      (node (ref "C27") (pin "2") (pinfunction "2_2") (pintype "passive"))
      (node (ref "U1") (pin "10") (pinfunction "RFOUT_10") (pintype "passive"))
    )
    (net (code "21") (name "Net-(U1-VCTRL)") (class "Default")
      (node (ref "C33") (pin "2") (pinfunction "2_2") (pintype "passive"))
      (node (ref "C34") (pin "2") (pinfunction "2_2") (pintype "passive"))
      (node (ref "R10") (pin "2") (pinfunction "2_2") (pintype "passive"))
      (node (ref "U1") (pin "14") (pinfunction "VCTRL_14") (pintype "passive"))
    )
    (net (code "22") (name "Net-(U1-VDD)") (class "Default")
      (node (ref "R8") (pin "1") (pinfunction "1_1") (pintype "passive"))
      (node (ref "U1") (pin "15") (pinfunction "VDD_15") (pintype "passive"))
    )
    (net (code "23") (name "Net-(U2-RF_IN)") (class "Default")
      (node (ref "C27") (pin "1") (pinfunction "1_1") (pintype "passive"))
      (node (ref "U2") (pin "1") (pinfunction "RF_IN_1") (pintype "passive"))
    )
    (net (code "24") (name "Net-(U2-RF_OUT)") (class "Default")
      (node (ref "C23") (pin "2") (pinfunction "2_2") (pintype "passive"))
      (node (ref "L4") (pin "2") (pinfunction "2_2") (pintype "passive"))
      (node (ref "U2") (pin "3") (pinfunction "RF_OUT_3") (pintype "passive"))
    )
    (net (code "25") (name "Net-(U3-MODE)") (class "Default")
      (node (ref "C18") (pin "2") (pinfunction "2_2") (pintype "passive"))
      (node (ref "C20") (pin "2") (pinfunction "2_2") (pintype "passive"))
      (node (ref "R6") (pin "2") (pinfunction "2_2") (pintype "passive"))
      (node (ref "U3") (pin "16") (pinfunction "MODE_16") (pintype "passive"))
    )
    (net (code "26") (name "Net-(U3-RFIN)") (class "Default")
      (node (ref "C22") (pin "2") (pinfunction "2_2") (pintype "passive"))
      (node (ref "U3") (pin "3") (pinfunction "RFIN_3") (pintype "passive"))
    )
    (net (code "27") (name "Net-(U3-RFOUT)") (class "Default")
      (node (ref "C14") (pin "2") (pinfunction "2_2") (pintype "passive"))
      (node (ref "U3") (pin "10") (pinfunction "RFOUT_10") (pintype "passive"))
    )
    (net (code "28") (name "Net-(U3-VCTRL)") (class "Default")
      (node (ref "C19") (pin "1") (pinfunction "1_1") (pintype "passive"))
      (node (ref "C21") (pin "1") (pinfunction "1_1") (pintype "passive"))
      (node (ref "R7") (pin "2") (pinfunction "2_2") (pintype "passive"))
      (node (ref "U3") (pin "14") (pinfunction "VCTRL_14") (pintype "passive"))
    )
    (net (code "29") (name "Net-(U3-VDD)") (class "Default")
      (node (ref "R5") (pin "1") (pinfunction "1_1") (pintype "passive"))
      (node (ref "U3") (pin "15") (pinfunction "VDD_15") (pintype "passive"))
    )
    (net (code "30") (name "Net-(U4-RF_IN)") (class "Default")
      (node (ref "C14") (pin "1") (pinfunction "1_1") (pintype "passive"))
      (node (ref "U4") (pin "1") (pinfunction "RF_IN_1") (pintype "passive"))
    )
    (net (code "31") (name "Net-(U4-RF_OUT)") (class "Default")
      (node (ref "C13") (pin "2") (pinfunction "2_2") (pintype "passive"))
      (node (ref "L2") (pin "2") (pinfunction "2_2") (pintype "passive"))
      (node (ref "U4") (pin "3") (pinfunction "RF_OUT_3") (pintype "passive"))
    )
    (net (code "32") (name "Net-(U5-50ohm_EXT)") (class "Default")
      (node (ref "R4") (pin "1") (pinfunction "1_1") (pintype "passive"))
      (node (ref "U5") (pin "6") (pinfunction "50ohm_EXT_6") (pintype "passive"))
    )
    (net (code "33") (name "Net-(U5-RF_OUT)") (class "Default")
      (node (ref "C9") (pin "2") (pinfunction "2_2") (pintype "passive"))
      (node (ref "U5") (pin "4") (pinfunction "RF_OUT_4") (pintype "output"))
    )
    (net (code "34") (name "Net-(U6-CLPF)") (class "Default")
      (node (ref "C3") (pin "2") (pinfunction "2_2") (pintype "passive"))
      (node (ref "U6") (pin "14") (pinfunction "CLPF_14") (pintype "passive"))
    )
    (net (code "35") (name "Net-(U6-INHI)") (class "Default")
      (node (ref "C1") (pin "2") (pinfunction "2_2") (pintype "passive"))
      (node (ref "U6") (pin "2") (pinfunction "INHI_2") (pintype "input"))
    )
    (net (code "36") (name "Net-(U6-INLO)") (class "Default")
      (node (ref "C2") (pin "2") (pinfunction "2_2") (pintype "passive"))
      (node (ref "U6") (pin "3") (pinfunction "INLO_3") (pintype "input"))
    )
    (net (code "37") (name "Net-(U6-TADJ)") (class "Default")
      (node (ref "R2") (pin "1") (pinfunction "1_1") (pintype "passive"))
      (node (ref "R3") (pin "2") (pinfunction "2_2") (pintype "passive"))
      (node (ref "U6") (pin "9") (pinfunction "TADJ_9") (pintype "input"))
    )
    (net (code "38") (name "unconnected-(U1-NC-Pad2)") (class "Default")
      (node (ref "U1") (pin "2") (pinfunction "NC_2") (pintype "passive+no_connect"))
    )
    (net (code "39") (name "unconnected-(U1-NC-Pad4)") (class "Default")
      (node (ref "U1") (pin "4") (pinfunction "NC_4") (pintype "passive+no_connect"))
    )
    (net (code "40") (name "unconnected-(U1-NC-Pad9)") (class "Default")
      (node (ref "U1") (pin "9") (pinfunction "NC_9") (pintype "passive+no_connect"))
    )
    (net (code "41") (name "unconnected-(U1-NC-Pad11)") (class "Default")
      (node (ref "U1") (pin "11") (pinfunction "NC_11") (pintype "passive+no_connect"))
    )
    (net (code "42") (name "unconnected-(U3-NC-Pad2)") (class "Default")
      (node (ref "U3") (pin "2") (pinfunction "NC_2") (pintype "passive+no_connect"))
    )
    (net (code "43") (name "unconnected-(U3-NC-Pad4)") (class "Default")
      (node (ref "U3") (pin "4") (pinfunction "NC_4") (pintype "passive+no_connect"))
    )
    (net (code "44") (name "unconnected-(U3-NC-Pad9)") (class "Default")
      (node (ref "U3") (pin "9") (pinfunction "NC_9") (pintype "passive+no_connect"))
    )
    (net (code "45") (name "unconnected-(U3-NC-Pad11)") (class "Default")
      (node (ref "U3") (pin "11") (pinfunction "NC_11") (pintype "passive+no_connect"))
    )
    (net (code "46") (name "unconnected-(U5-NC-Pad5)") (class "Default")
      (node (ref "U5") (pin "5") (pinfunction "NC_5") (pintype "passive+no_connect"))
    )
  )
)
